# esp12-adapter.net
KiCad netlist of a schematic drawn in EAGLE
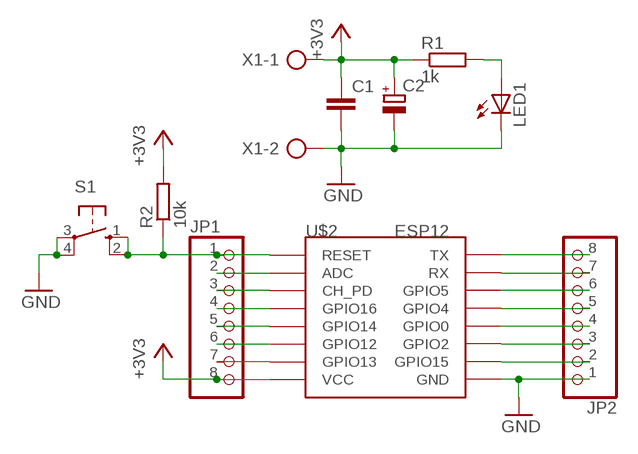
[diagram p0: schematic, sheet 1]

(export (version "E")
  (design (tool "Eeschema 10.0.6"))
  (components
    (comp (ref "C1")
      (value "C-EU025-025X050")
      (footprint "eagle-import:C025-025X050")
      (libsource (lib "eagle-import") (part "C-EU025-025X050"))
    )
    (comp (ref "C2")
      (value "CPOL-EUE3.5-10")
      (footprint "eagle-import:E3,5-10")
      (libsource (lib "eagle-import") (part "CPOL-EUE3.5-10"))
    )
    (comp (ref "JP1")
      (value "PINHD-1X8")
      (footprint "eagle-import:1X08")
      (libsource (lib "eagle-import") (part "PINHD-1X8"))
    )
    (comp (ref "JP2")
      (value "PINHD-1X8")
      (footprint "eagle-import:1X08")
      (libsource (lib "eagle-import") (part "PINHD-1X8"))
    )
    (comp (ref "LED1")
      (value "LED5MM")
      (footprint "eagle-import:LED5MM")
      (libsource (lib "eagle-import") (part "LED5MM"))
    )
    (comp (ref "R1")
      (value "1k")
      (footprint "eagle-import:R1206")
      (libsource (lib "eagle-import") (part "R-EU_R1206"))
    )
    (comp (ref "R2")
      (value "10k")
      (footprint "eagle-import:R1206")
      (libsource (lib "eagle-import") (part "R-EU_R1206"))
    )
    (comp (ref "S1")
      (value "10-XX")
      (footprint "eagle-import:B3F-10XX")
      (fields (field (name "MPN") "B3F-1000"))
      (libsource (lib "eagle-import") (part "10-XX"))
    )
    (comp (ref "U$2")
      (value "ESP12")
      (footprint "eagle-import:ESP12")
      (libsource (lib "eagle-import") (part "ESP12"))
    )
    (comp (ref "X1")
      (value "AK300/2")
      (footprint "eagle-import:AK300_2")
      (libsource (lib "eagle-import") (part "AK300/2"))
    )
  )
  (nets
    (net (code "1") (name "+3V3") (class "Default")
      (node (ref "C1") (pin "1") (pinfunction "1_1") (pintype "passive"))
      (node (ref "C2") (pin "+") (pinfunction "+_+") (pintype "passive"))
      (node (ref "JP1") (pin "8") (pinfunction "8_8") (pintype "passive"))
      (node (ref "R1") (pin "1") (pinfunction "1_1") (pintype "passive"))
      (node (ref "R2") (pin "2") (pinfunction "2_2") (pintype "passive"))
      (node (ref "U$2") (pin "VCC") (pinfunction "VCC_VCC") (pintype "bidirectional"))
      (node (ref "X1") (pin "1") (pinfunction "KL_1") (pintype "passive"))
    )
    (net (code "2") (name "GND") (class "Default")
      (node (ref "C1") (pin "2") (pinfunction "2_2") (pintype "passive"))
      (node (ref "C2") (pin "-") (pinfunction "-_-") (pintype "passive"))
      (node (ref "JP2") (pin "1") (pinfunction "1_1") (pintype "passive"))
      (node (ref "LED1") (pin "K") (pinfunction "C_K") (pintype "passive"))
      (node (ref "S1") (pin "3") (pinfunction "P_3") (pintype "passive"))
      (node (ref "S1") (pin "4") (pinfunction "P1_4") (pintype "passive"))
      (node (ref "U$2") (pin "GND") (pinfunction "GND_GND") (pintype "bidirectional"))
      (node (ref "X1") (pin "2") (pinfunction "KL_2") (pintype "passive"))
    )
    (net (code "3") (name "Net-(JP1-Pad2)") (class "Default")
      (node (ref "JP1") (pin "2") (pinfunction "2_2") (pintype "passive"))
      (node (ref "U$2") (pin "ADC") (pinfunction "ADC_ADC") (pintype "bidirectional"))
    )
    (net (code "4") (name "Net-(JP1-Pad3)") (class "Default")
      (node (ref "JP1") (pin "3") (pinfunction "3_3") (pintype "passive"))
      (node (ref "U$2") (pin "CH_PD") (pinfunction "CH_PD_CH_PD") (pintype "bidirectional"))
    )
    (net (code "5") (name "Net-(JP1-Pad4)") (class "Default")
      (node (ref "JP1") (pin "4") (pinfunction "4_4") (pintype "passive"))
      (node (ref "U$2") (pin "GPIO16") (pinfunction "GPIO16_GPIO16") (pintype "bidirectional"))
    )
    (net (code "6") (name "Net-(JP1-Pad5)") (class "Default")
      (node (ref "JP1") (pin "5") (pinfunction "5_5") (pintype "passive"))
      (node (ref "U$2") (pin "GPIO14") (pinfunction "GPIO14_GPIO14") (pintype "bidirectional"))
    )
    (net (code "7") (name "Net-(JP1-Pad6)") (class "Default")
      (node (ref "JP1") (pin "6") (pinfunction "6_6") (pintype "passive"))
      (node (ref "U$2") (pin "GPIO12") (pinfunction "GPIO12_GPIO12") (pintype "bidirectional"))
    )
    (net (code "8") (name "Net-(JP1-Pad7)") (class "Default")
      (node (ref "JP1") (pin "7") (pinfunction "7_7") (pintype "passive"))
      (node (ref "U$2") (pin "GPIO13") (pinfunction "GPIO13_GPIO13") (pintype "bidirectional"))
    )
    (net (code "9") (name "Net-(JP2-Pad2)") (class "Default")
      (node (ref "JP2") (pin "2") (pinfunction "2_2") (pintype "passive"))
      (node (ref "U$2") (pin "GPIO15") (pinfunction "GPIO15_GPIO15") (pintype "bidirectional"))
    )
    (net (code "10") (name "Net-(JP2-Pad3)") (class "Default")
      (node (ref "JP2") (pin "3") (pinfunction "3_3") (pintype "passive"))
      (node (ref "U$2") (pin "GPIO2") (pinfunction "GPIO2_GPIO2") (pintype "bidirectional"))
    )
    (net (code "11") (name "Net-(JP2-Pad4)") (class "Default")
      (node (ref "JP2") (pin "4") (pinfunction "4_4") (pintype "passive"))
      (node (ref "U$2") (pin "GPIO0") (pinfunction "GPIO0_GPIO0") (pintype "bidirectional"))
    )
    (net (code "12") (name "Net-(JP2-Pad7)") (class "Default")
      (node (ref "JP2") (pin "7") (pinfunction "7_7") (pintype "passive"))
      (node (ref "U$2") (pin "RX") (pinfunction "RX_RX") (pintype "bidirectional"))
    )
    (net (code "13") (name "Net-(JP2-Pad8)") (class "Default")
      (node (ref "JP2") (pin "8") (pinfunction "8_8") (pintype "passive"))
      (node (ref "U$2") (pin "TX") (pinfunction "TX_TX") (pintype "bidirectional"))
    )
    (net (code "14") (name "Net-(LED1-PadA)") (class "Default")
      (node (ref "LED1") (pin "A") (pinfunction "A_A") (pintype "passive"))
      (node (ref "R1") (pin "2") (pinfunction "2_2") (pintype "passive"))
    )
    (net (code "15") (name "Net-(S1-S)") (class "Default")
      (node (ref "JP1") (pin "1") (pinfunction "1_1") (pintype "passive"))
      (node (ref "R2") (pin "1") (pinfunction "1_1") (pintype "passive"))
      (node (ref "S1") (pin "1") (pinfunction "S_1") (pintype "passive"))
      (node (ref "S1") (pin "2") (pinfunction "S1_2") (pintype "passive"))
      (node (ref "U$2") (pin "RESET") (pinfunction "RESET_RESET") (pintype "bidirectional"))
    )
    (net (code "16") (name "Net-(U$2-GPIO4)") (class "Default")
      (node (ref "JP2") (pin "5") (pinfunction "5_5") (pintype "passive"))
      (node (ref "U$2") (pin "GPIO5") (pinfunction "GPIO4_GPIO5") (pintype "bidirectional"))
    )
    (net (code "17") (name "Net-(U$2-GPIO5)") (class "Default")
      (node (ref "JP2") (pin "6") (pinfunction "6_6") (pintype "passive"))
      (node (ref "U$2") (pin "GPIO4") (pinfunction "GPIO5_GPIO4") (pintype "bidirectional"))
    )
  )
)
